# PCB-BI8-2x8.net
KiCad netlist of a schematic drawn in EAGLE
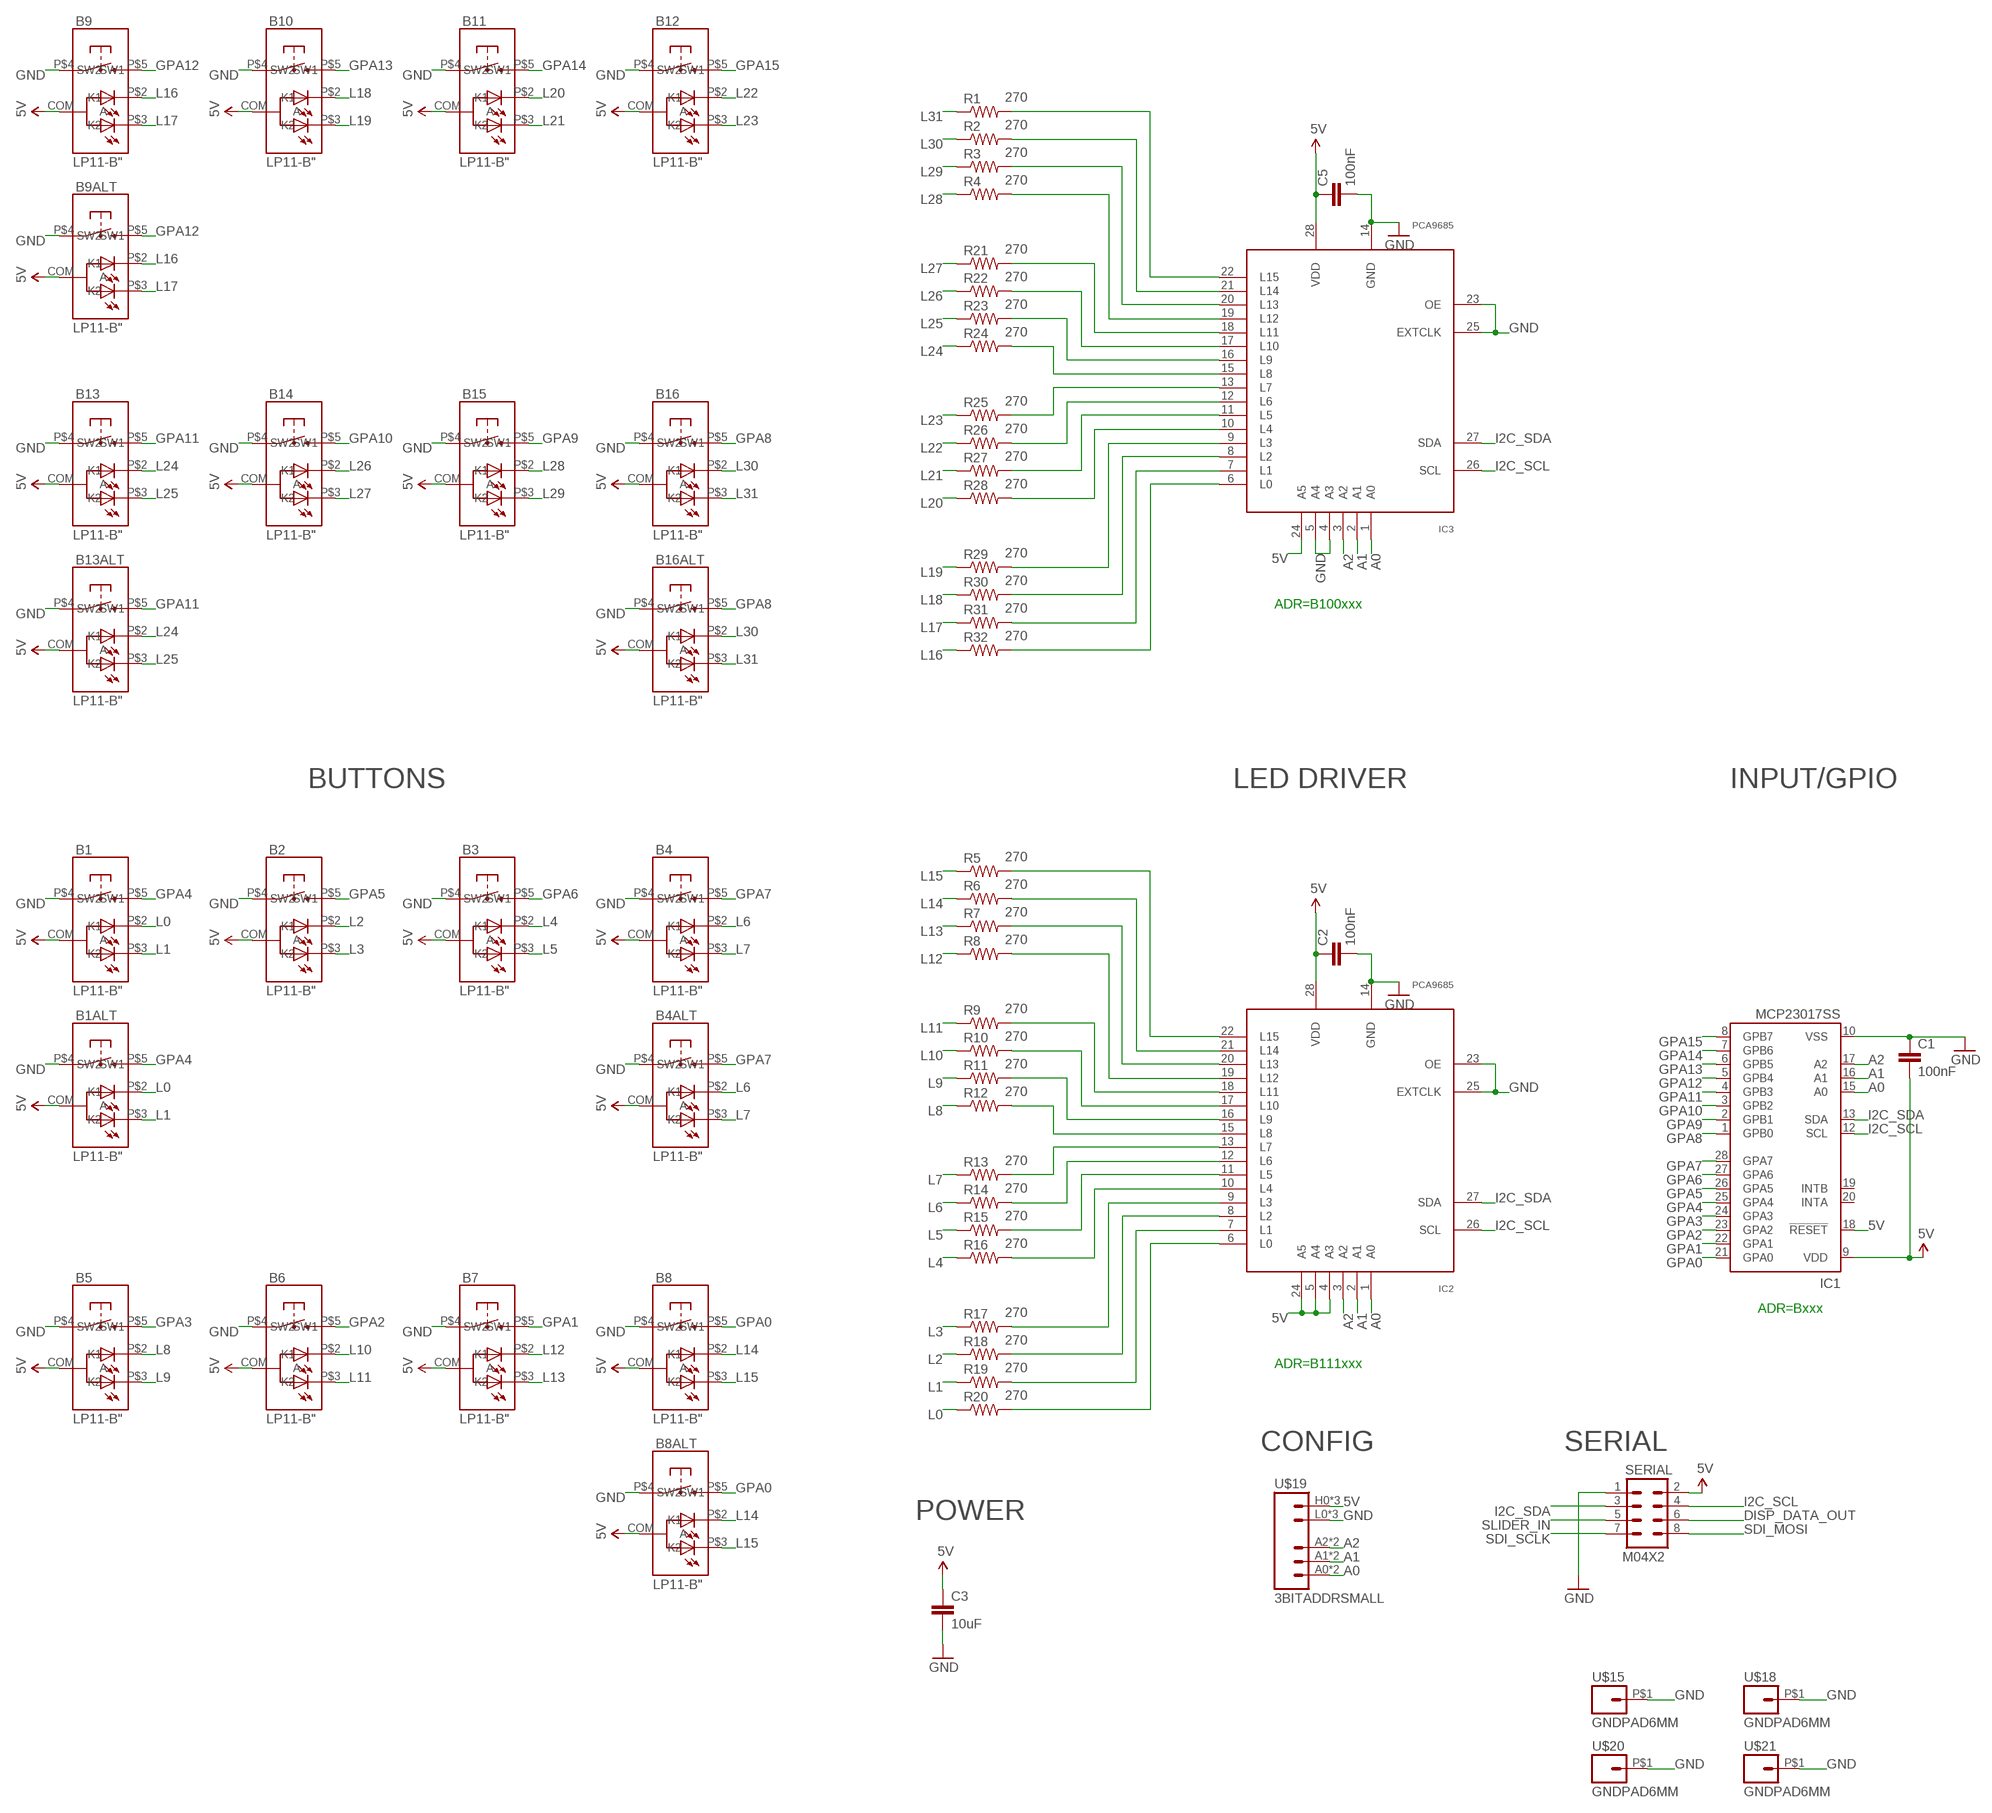
[diagram p0: schematic, sheet 1]

(export (version "E")
  (design (tool "Eeschema 10.0.6"))
  (components
    (comp (ref "B1")
      (value "LP11-B\"")
      (footprint "eagle-import:LP11")
      (libsource (lib "eagle-import") (part "LP11-B{dblquote}"))
    )
    (comp (ref "B1ALT")
      (value "LP11-B\"")
      (footprint "eagle-import:LP11")
      (libsource (lib "eagle-import") (part "LP11-B{dblquote}"))
    )
    (comp (ref "B2")
      (value "LP11-B\"")
      (footprint "eagle-import:LP11")
      (libsource (lib "eagle-import") (part "LP11-B{dblquote}"))
    )
    (comp (ref "B3")
      (value "LP11-B\"")
      (footprint "eagle-import:LP11")
      (libsource (lib "eagle-import") (part "LP11-B{dblquote}"))
    )
    (comp (ref "B4")
      (value "LP11-B\"")
      (footprint "eagle-import:LP11")
      (libsource (lib "eagle-import") (part "LP11-B{dblquote}"))
    )
    (comp (ref "B4ALT")
      (value "LP11-B\"")
      (footprint "eagle-import:LP11")
      (libsource (lib "eagle-import") (part "LP11-B{dblquote}"))
    )
    (comp (ref "B5")
      (value "LP11-B\"")
      (footprint "eagle-import:LP11")
      (libsource (lib "eagle-import") (part "LP11-B{dblquote}"))
    )
    (comp (ref "B6")
      (value "LP11-B\"")
      (footprint "eagle-import:LP11")
      (libsource (lib "eagle-import") (part "LP11-B{dblquote}"))
    )
    (comp (ref "B7")
      (value "LP11-B\"")
      (footprint "eagle-import:LP11")
      (libsource (lib "eagle-import") (part "LP11-B{dblquote}"))
    )
    (comp (ref "B8")
      (value "LP11-B\"")
      (footprint "eagle-import:LP11")
      (libsource (lib "eagle-import") (part "LP11-B{dblquote}"))
    )
    (comp (ref "B8ALT")
      (value "LP11-B\"")
      (footprint "eagle-import:LP11")
      (libsource (lib "eagle-import") (part "LP11-B{dblquote}"))
    )
    (comp (ref "B9")
      (value "LP11-B\"")
      (footprint "eagle-import:LP11")
      (libsource (lib "eagle-import") (part "LP11-B{dblquote}"))
    )
    (comp (ref "B9ALT")
      (value "LP11-B\"")
      (footprint "eagle-import:LP11")
      (libsource (lib "eagle-import") (part "LP11-B{dblquote}"))
    )
    (comp (ref "B10")
      (value "LP11-B\"")
      (footprint "eagle-import:LP11")
      (libsource (lib "eagle-import") (part "LP11-B{dblquote}"))
    )
    (comp (ref "B11")
      (value "LP11-B\"")
      (footprint "eagle-import:LP11")
      (libsource (lib "eagle-import") (part "LP11-B{dblquote}"))
    )
    (comp (ref "B12")
      (value "LP11-B\"")
      (footprint "eagle-import:LP11")
      (libsource (lib "eagle-import") (part "LP11-B{dblquote}"))
    )
    (comp (ref "B13")
      (value "LP11-B\"")
      (footprint "eagle-import:LP11")
      (libsource (lib "eagle-import") (part "LP11-B{dblquote}"))
    )
    (comp (ref "B13ALT")
      (value "LP11-B\"")
      (footprint "eagle-import:LP11")
      (libsource (lib "eagle-import") (part "LP11-B{dblquote}"))
    )
    (comp (ref "B14")
      (value "LP11-B\"")
      (footprint "eagle-import:LP11")
      (libsource (lib "eagle-import") (part "LP11-B{dblquote}"))
    )
    (comp (ref "B15")
      (value "LP11-B\"")
      (footprint "eagle-import:LP11")
      (libsource (lib "eagle-import") (part "LP11-B{dblquote}"))
    )
    (comp (ref "B16")
      (value "LP11-B\"")
      (footprint "eagle-import:LP11")
      (libsource (lib "eagle-import") (part "LP11-B{dblquote}"))
    )
    (comp (ref "B16ALT")
      (value "LP11-B\"")
      (footprint "eagle-import:LP11")
      (libsource (lib "eagle-import") (part "LP11-B{dblquote}"))
    )
    (comp (ref "C1")
      (value "100nF")
      (footprint "eagle-import:0603-CAP")
      (libsource (lib "eagle-import") (part "CAP0603-CAP"))
    )
    (comp (ref "C2")
      (value "100nF")
      (footprint "eagle-import:0603-CAP")
      (libsource (lib "eagle-import") (part "CAP0603-CAP"))
    )
    (comp (ref "C3")
      (value "10uF")
      (footprint "eagle-import:0805")
      (libsource (lib "eagle-import") (part "CAP0805"))
    )
    (comp (ref "C5")
      (value "100nF")
      (footprint "eagle-import:0603-CAP")
      (libsource (lib "eagle-import") (part "CAP0603-CAP"))
    )
    (comp (ref "IC1")
      (value "MCP23017SS")
      (footprint "eagle-import:SSOP28")
      (fields
        (field (name "MF") "MICROCHIP")
        (field (name "MPN") "MCP23017-E/SS")
        (field (name "MPN_1") "MCP23017-E/SS")
        (field (name "OC_FARNELL") "1467674")
        (field (name "OC_NEWARK") "31K2960")
      )
      (libsource (lib "eagle-import") (part "MCP23017SS"))
    )
    (comp (ref "IC2")
      (value "PCA9685")
      (footprint "eagle-import:TSSOP28")
      (libsource (lib "eagle-import") (part "PCA9685"))
    )
    (comp (ref "IC3")
      (value "PCA9685")
      (footprint "eagle-import:TSSOP28")
      (libsource (lib "eagle-import") (part "PCA9685"))
    )
    (comp (ref "R1")
      (value "270")
      (footprint "eagle-import:0603-RES")
      (libsource (lib "eagle-import") (part "RESISTOR0603-RES"))
    )
    (comp (ref "R2")
      (value "270")
      (footprint "eagle-import:0603-RES")
      (libsource (lib "eagle-import") (part "RESISTOR0603-RES"))
    )
    (comp (ref "R3")
      (value "270")
      (footprint "eagle-import:0603-RES")
      (libsource (lib "eagle-import") (part "RESISTOR0603-RES"))
    )
    (comp (ref "R4")
      (value "270")
      (footprint "eagle-import:0603-RES")
      (libsource (lib "eagle-import") (part "RESISTOR0603-RES"))
    )
    (comp (ref "R5")
      (value "270")
      (footprint "eagle-import:0603-RES")
      (libsource (lib "eagle-import") (part "RESISTOR0603-RES"))
    )
    (comp (ref "R6")
      (value "270")
      (footprint "eagle-import:0603-RES")
      (libsource (lib "eagle-import") (part "RESISTOR0603-RES"))
    )
    (comp (ref "R7")
      (value "270")
      (footprint "eagle-import:0603-RES")
      (libsource (lib "eagle-import") (part "RESISTOR0603-RES"))
    )
    (comp (ref "R8")
      (value "270")
      (footprint "eagle-import:0603-RES")
      (libsource (lib "eagle-import") (part "RESISTOR0603-RES"))
    )
    (comp (ref "R9")
      (value "270")
      (footprint "eagle-import:0603-RES")
      (libsource (lib "eagle-import") (part "RESISTOR0603-RES"))
    )
    (comp (ref "R10")
      (value "270")
      (footprint "eagle-import:0603-RES")
      (libsource (lib "eagle-import") (part "RESISTOR0603-RES"))
    )
    (comp (ref "R11")
      (value "270")
      (footprint "eagle-import:0603-RES")
      (libsource (lib "eagle-import") (part "RESISTOR0603-RES"))
    )
    (comp (ref "R12")
      (value "270")
      (footprint "eagle-import:0603-RES")
      (libsource (lib "eagle-import") (part "RESISTOR0603-RES"))
    )
    (comp (ref "R13")
      (value "270")
      (footprint "eagle-import:0603-RES")
      (libsource (lib "eagle-import") (part "RESISTOR0603-RES"))
    )
    (comp (ref "R14")
      (value "270")
      (footprint "eagle-import:0603-RES")
      (libsource (lib "eagle-import") (part "RESISTOR0603-RES"))
    )
    (comp (ref "R15")
      (value "270")
      (footprint "eagle-import:0603-RES")
      (libsource (lib "eagle-import") (part "RESISTOR0603-RES"))
    )
    (comp (ref "R16")
      (value "270")
      (footprint "eagle-import:0603-RES")
      (libsource (lib "eagle-import") (part "RESISTOR0603-RES"))
    )
    (comp (ref "R17")
      (value "270")
      (footprint "eagle-import:0603-RES")
      (libsource (lib "eagle-import") (part "RESISTOR0603-RES"))
    )
    (comp (ref "R18")
      (value "270")
      (footprint "eagle-import:0603-RES")
      (libsource (lib "eagle-import") (part "RESISTOR0603-RES"))
    )
    (comp (ref "R19")
      (value "270")
      (footprint "eagle-import:0603-RES")
      (libsource (lib "eagle-import") (part "RESISTOR0603-RES"))
    )
    (comp (ref "R20")
      (value "270")
      (footprint "eagle-import:0603-RES")
      (libsource (lib "eagle-import") (part "RESISTOR0603-RES"))
    )
    (comp (ref "R21")
      (value "270")
      (footprint "eagle-import:0603-RES")
      (libsource (lib "eagle-import") (part "RESISTOR0603-RES"))
    )
    (comp (ref "R22")
      (value "270")
      (footprint "eagle-import:0603-RES")
      (libsource (lib "eagle-import") (part "RESISTOR0603-RES"))
    )
    (comp (ref "R23")
      (value "270")
      (footprint "eagle-import:0603-RES")
      (libsource (lib "eagle-import") (part "RESISTOR0603-RES"))
    )
    (comp (ref "R24")
      (value "270")
      (footprint "eagle-import:0603-RES")
      (libsource (lib "eagle-import") (part "RESISTOR0603-RES"))
    )
    (comp (ref "R25")
      (value "270")
      (footprint "eagle-import:0603-RES")
      (libsource (lib "eagle-import") (part "RESISTOR0603-RES"))
    )
    (comp (ref "R26")
      (value "270")
      (footprint "eagle-import:0603-RES")
      (libsource (lib "eagle-import") (part "RESISTOR0603-RES"))
    )
    (comp (ref "R27")
      (value "270")
      (footprint "eagle-import:0603-RES")
      (libsource (lib "eagle-import") (part "RESISTOR0603-RES"))
    )
    (comp (ref "R28")
      (value "270")
      (footprint "eagle-import:0603-RES")
      (libsource (lib "eagle-import") (part "RESISTOR0603-RES"))
    )
    (comp (ref "R29")
      (value "270")
      (footprint "eagle-import:0603-RES")
      (libsource (lib "eagle-import") (part "RESISTOR0603-RES"))
    )
    (comp (ref "R30")
      (value "270")
      (footprint "eagle-import:0603-RES")
      (libsource (lib "eagle-import") (part "RESISTOR0603-RES"))
    )
    (comp (ref "R31")
      (value "270")
      (footprint "eagle-import:0603-RES")
      (libsource (lib "eagle-import") (part "RESISTOR0603-RES"))
    )
    (comp (ref "R32")
      (value "270")
      (footprint "eagle-import:0603-RES")
      (libsource (lib "eagle-import") (part "RESISTOR0603-RES"))
    )
    (comp (ref "SERIAL")
      (value "M04X2")
      (footprint "eagle-import:2X4")
      (libsource (lib "eagle-import") (part "M04X2"))
    )
    (comp (ref "U$15")
      (value "GNDPAD6MM")
      (footprint "eagle-import:3.2MMPAD6MM")
      (libsource (lib "eagle-import") (part "GNDPAD6MM"))
    )
    (comp (ref "U$18")
      (value "GNDPAD6MM")
      (footprint "eagle-import:3.2MMPAD6MM")
      (libsource (lib "eagle-import") (part "GNDPAD6MM"))
    )
    (comp (ref "U$19")
      (value "3BITADDRSMALL")
      (footprint "eagle-import:3BITADDR_SMALL")
      (libsource (lib "eagle-import") (part "3BITADDRSMALL"))
    )
    (comp (ref "U$20")
      (value "GNDPAD6MM")
      (footprint "eagle-import:3.2MMPAD6MM")
      (libsource (lib "eagle-import") (part "GNDPAD6MM"))
    )
    (comp (ref "U$21")
      (value "GNDPAD6MM")
      (footprint "eagle-import:3.2MMPAD6MM")
      (libsource (lib "eagle-import") (part "GNDPAD6MM"))
    )
  )
  (nets
    (net (code "1") (name "5V") (class "Default")
      (node (ref "B1") (pin "COM") (pinfunction "A_COM") (pintype "bidirectional"))
      (node (ref "B10") (pin "COM") (pinfunction "A_COM") (pintype "bidirectional"))
      (node (ref "B11") (pin "COM") (pinfunction "A_COM") (pintype "bidirectional"))
      (node (ref "B12") (pin "COM") (pinfunction "A_COM") (pintype "bidirectional"))
      (node (ref "B13") (pin "COM") (pinfunction "A_COM") (pintype "bidirectional"))
      (node (ref "B13ALT") (pin "COM") (pinfunction "A_COM") (pintype "bidirectional"))
      (node (ref "B14") (pin "COM") (pinfunction "A_COM") (pintype "bidirectional"))
      (node (ref "B15") (pin "COM") (pinfunction "A_COM") (pintype "bidirectional"))
      (node (ref "B16") (pin "COM") (pinfunction "A_COM") (pintype "bidirectional"))
      (node (ref "B16ALT") (pin "COM") (pinfunction "A_COM") (pintype "bidirectional"))
      (node (ref "B1ALT") (pin "COM") (pinfunction "A_COM") (pintype "bidirectional"))
      (node (ref "B2") (pin "COM") (pinfunction "A_COM") (pintype "bidirectional"))
      (node (ref "B3") (pin "COM") (pinfunction "A_COM") (pintype "bidirectional"))
      (node (ref "B4") (pin "COM") (pinfunction "A_COM") (pintype "bidirectional"))
      (node (ref "B4ALT") (pin "COM") (pinfunction "A_COM") (pintype "bidirectional"))
      (node (ref "B5") (pin "COM") (pinfunction "A_COM") (pintype "bidirectional"))
      (node (ref "B6") (pin "COM") (pinfunction "A_COM") (pintype "bidirectional"))
      (node (ref "B7") (pin "COM") (pinfunction "A_COM") (pintype "bidirectional"))
      (node (ref "B8") (pin "COM") (pinfunction "A_COM") (pintype "bidirectional"))
      (node (ref "B8ALT") (pin "COM") (pinfunction "A_COM") (pintype "bidirectional"))
      (node (ref "B9") (pin "COM") (pinfunction "A_COM") (pintype "bidirectional"))
      (node (ref "B9ALT") (pin "COM") (pinfunction "A_COM") (pintype "bidirectional"))
      (node (ref "C1") (pin "2") (pinfunction "2_2") (pintype "passive"))
      (node (ref "C2") (pin "1") (pinfunction "1_1") (pintype "passive"))
      (node (ref "C3") (pin "1") (pinfunction "1_1") (pintype "passive"))
      (node (ref "C5") (pin "1") (pinfunction "1_1") (pintype "passive"))
      (node (ref "IC1") (pin "18") (pinfunction "~{RESET}_18") (pintype "input"))
      (node (ref "IC1") (pin "9") (pinfunction "VDD_9") (pintype "power_in"))
      (node (ref "IC2") (pin "24") (pinfunction "A5_24") (pintype "input"))
      (node (ref "IC2") (pin "28") (pinfunction "VDD_28") (pintype "power_in"))
      (node (ref "IC2") (pin "4") (pinfunction "A3_4") (pintype "input"))
      (node (ref "IC2") (pin "5") (pinfunction "A4_5") (pintype "input"))
      (node (ref "IC3") (pin "24") (pinfunction "A5_24") (pintype "input"))
      (node (ref "IC3") (pin "28") (pinfunction "VDD_28") (pintype "power_in"))
      (node (ref "SERIAL") (pin "2") (pinfunction "2_2") (pintype "passive"))
      (node (ref "U$19") (pin "H0") (pinfunction "VCC_H0") (pintype "passive"))
      (node (ref "U$19") (pin "H1") (pinfunction "VCC_H1") (pintype "passive"))
      (node (ref "U$19") (pin "H2") (pinfunction "VCC_H2") (pintype "passive"))
    )
    (net (code "2") (name "A0") (class "Default")
      (node (ref "IC1") (pin "15") (pinfunction "A0_15") (pintype "input"))
      (node (ref "IC2") (pin "1") (pinfunction "A0_1") (pintype "input"))
      (node (ref "IC3") (pin "1") (pinfunction "A0_1") (pintype "input"))
      (node (ref "U$19") (pin "A0") (pinfunction "A0_A0") (pintype "passive"))
      (node (ref "U$19") (pin "AS0") (pinfunction "A0_AS0") (pintype "passive"))
    )
    (net (code "3") (name "A1") (class "Default")
      (node (ref "IC1") (pin "16") (pinfunction "A1_16") (pintype "input"))
      (node (ref "IC2") (pin "2") (pinfunction "A1_2") (pintype "input"))
      (node (ref "IC3") (pin "2") (pinfunction "A1_2") (pintype "input"))
      (node (ref "U$19") (pin "A1") (pinfunction "A1_A1") (pintype "passive"))
      (node (ref "U$19") (pin "AS1") (pinfunction "A1_AS1") (pintype "passive"))
    )
    (net (code "4") (name "A2") (class "Default")
      (node (ref "IC1") (pin "17") (pinfunction "A2_17") (pintype "input"))
      (node (ref "IC2") (pin "3") (pinfunction "A2_3") (pintype "input"))
      (node (ref "IC3") (pin "3") (pinfunction "A2_3") (pintype "input"))
      (node (ref "U$19") (pin "A2") (pinfunction "A2_A2") (pintype "passive"))
      (node (ref "U$19") (pin "AS2") (pinfunction "A2_AS2") (pintype "passive"))
    )
    (net (code "5") (name "DISP_DATA_OUT") (class "Default")
      (node (ref "SERIAL") (pin "6") (pinfunction "6_6") (pintype "passive"))
    )
    (net (code "6") (name "GND") (class "Default")
      (node (ref "B1") (pin "P$4") (pinfunction "SW1_P$4") (pintype "bidirectional"))
      (node (ref "B10") (pin "P$4") (pinfunction "SW1_P$4") (pintype "bidirectional"))
      (node (ref "B11") (pin "P$4") (pinfunction "SW1_P$4") (pintype "bidirectional"))
      (node (ref "B12") (pin "P$4") (pinfunction "SW1_P$4") (pintype "bidirectional"))
      (node (ref "B13") (pin "P$4") (pinfunction "SW1_P$4") (pintype "bidirectional"))
      (node (ref "B13ALT") (pin "P$4") (pinfunction "SW1_P$4") (pintype "bidirectional"))
      (node (ref "B14") (pin "P$4") (pinfunction "SW1_P$4") (pintype "bidirectional"))
      (node (ref "B15") (pin "P$4") (pinfunction "SW1_P$4") (pintype "bidirectional"))
      (node (ref "B16") (pin "P$4") (pinfunction "SW1_P$4") (pintype "bidirectional"))
      (node (ref "B16ALT") (pin "P$4") (pinfunction "SW1_P$4") (pintype "bidirectional"))
      (node (ref "B1ALT") (pin "P$4") (pinfunction "SW1_P$4") (pintype "bidirectional"))
      (node (ref "B2") (pin "P$4") (pinfunction "SW1_P$4") (pintype "bidirectional"))
      (node (ref "B3") (pin "P$4") (pinfunction "SW1_P$4") (pintype "bidirectional"))
      (node (ref "B4") (pin "P$4") (pinfunction "SW1_P$4") (pintype "bidirectional"))
      (node (ref "B4ALT") (pin "P$4") (pinfunction "SW1_P$4") (pintype "bidirectional"))
      (node (ref "B5") (pin "P$4") (pinfunction "SW1_P$4") (pintype "bidirectional"))
      (node (ref "B6") (pin "P$4") (pinfunction "SW1_P$4") (pintype "bidirectional"))
      (node (ref "B7") (pin "P$4") (pinfunction "SW1_P$4") (pintype "bidirectional"))
      (node (ref "B8") (pin "P$4") (pinfunction "SW1_P$4") (pintype "bidirectional"))
      (node (ref "B8ALT") (pin "P$4") (pinfunction "SW1_P$4") (pintype "bidirectional"))
      (node (ref "B9") (pin "P$4") (pinfunction "SW1_P$4") (pintype "bidirectional"))
      (node (ref "B9ALT") (pin "P$4") (pinfunction "SW1_P$4") (pintype "bidirectional"))
      (node (ref "C1") (pin "1") (pinfunction "1_1") (pintype "passive"))
      (node (ref "C2") (pin "2") (pinfunction "2_2") (pintype "passive"))
      (node (ref "C3") (pin "2") (pinfunction "2_2") (pintype "passive"))
      (node (ref "C5") (pin "2") (pinfunction "2_2") (pintype "passive"))
      (node (ref "IC1") (pin "10") (pinfunction "VSS_10") (pintype "power_in"))
      (node (ref "IC2") (pin "14") (pinfunction "GND_14") (pintype "power_in"))
      (node (ref "IC2") (pin "23") (pinfunction "OE_23") (pintype "input"))
      (node (ref "IC2") (pin "25") (pinfunction "EXTCLK_25") (pintype "input"))
      (node (ref "IC3") (pin "14") (pinfunction "GND_14") (pintype "power_in"))
      (node (ref "IC3") (pin "23") (pinfunction "OE_23") (pintype "input"))
      (node (ref "IC3") (pin "25") (pinfunction "EXTCLK_25") (pintype "input"))
      (node (ref "IC3") (pin "4") (pinfunction "A3_4") (pintype "input"))
      (node (ref "IC3") (pin "5") (pinfunction "A4_5") (pintype "input"))
      (node (ref "SERIAL") (pin "1") (pinfunction "1_1") (pintype "passive"))
      (node (ref "U$15") (pin "P$1") (pinfunction "1_P$1") (pintype "passive"))
      (node (ref "U$18") (pin "P$1") (pinfunction "1_P$1") (pintype "passive"))
      (node (ref "U$19") (pin "L0") (pinfunction "GND_L0") (pintype "passive"))
      (node (ref "U$19") (pin "L1") (pinfunction "GND_L1") (pintype "passive"))
      (node (ref "U$19") (pin "L2") (pinfunction "GND_L2") (pintype "passive"))
      (node (ref "U$20") (pin "P$1") (pinfunction "1_P$1") (pintype "passive"))
      (node (ref "U$21") (pin "P$1") (pinfunction "1_P$1") (pintype "passive"))
    )
    (net (code "7") (name "GPA0") (class "Default")
      (node (ref "B8") (pin "P$5") (pinfunction "SW2_P$5") (pintype "bidirectional"))
      (node (ref "B8ALT") (pin "P$5") (pinfunction "SW2_P$5") (pintype "bidirectional"))
      (node (ref "IC1") (pin "21") (pinfunction "GPA0_21") (pintype "bidirectional"))
    )
    (net (code "8") (name "GPA1") (class "Default")
      (node (ref "B7") (pin "P$5") (pinfunction "SW2_P$5") (pintype "bidirectional"))
      (node (ref "IC1") (pin "22") (pinfunction "GPA1_22") (pintype "bidirectional"))
    )
    (net (code "9") (name "GPA2") (class "Default")
      (node (ref "B6") (pin "P$5") (pinfunction "SW2_P$5") (pintype "bidirectional"))
      (node (ref "IC1") (pin "23") (pinfunction "GPA2_23") (pintype "bidirectional"))
    )
    (net (code "10") (name "GPA3") (class "Default")
      (node (ref "B5") (pin "P$5") (pinfunction "SW2_P$5") (pintype "bidirectional"))
      (node (ref "IC1") (pin "24") (pinfunction "GPA3_24") (pintype "bidirectional"))
    )
    (net (code "11") (name "GPA4") (class "Default")
      (node (ref "B1") (pin "P$5") (pinfunction "SW2_P$5") (pintype "bidirectional"))
      (node (ref "B1ALT") (pin "P$5") (pinfunction "SW2_P$5") (pintype "bidirectional"))
      (node (ref "IC1") (pin "25") (pinfunction "GPA4_25") (pintype "bidirectional"))
    )
    (net (code "12") (name "GPA5") (class "Default")
      (node (ref "B2") (pin "P$5") (pinfunction "SW2_P$5") (pintype "bidirectional"))
      (node (ref "IC1") (pin "26") (pinfunction "GPA5_26") (pintype "bidirectional"))
    )
    (net (code "13") (name "GPA6") (class "Default")
      (node (ref "B3") (pin "P$5") (pinfunction "SW2_P$5") (pintype "bidirectional"))
      (node (ref "IC1") (pin "27") (pinfunction "GPA6_27") (pintype "bidirectional"))
    )
    (net (code "14") (name "GPA7") (class "Default")
      (node (ref "B4") (pin "P$5") (pinfunction "SW2_P$5") (pintype "bidirectional"))
      (node (ref "B4ALT") (pin "P$5") (pinfunction "SW2_P$5") (pintype "bidirectional"))
      (node (ref "IC1") (pin "28") (pinfunction "GPA7_28") (pintype "bidirectional"))
    )
    (net (code "15") (name "GPA8") (class "Default")
      (node (ref "B16") (pin "P$5") (pinfunction "SW2_P$5") (pintype "bidirectional"))
      (node (ref "B16ALT") (pin "P$5") (pinfunction "SW2_P$5") (pintype "bidirectional"))
      (node (ref "IC1") (pin "1") (pinfunction "GPB0_1") (pintype "bidirectional"))
    )
    (net (code "16") (name "GPA9") (class "Default")
      (node (ref "B15") (pin "P$5") (pinfunction "SW2_P$5") (pintype "bidirectional"))
      (node (ref "IC1") (pin "2") (pinfunction "GPB1_2") (pintype "bidirectional"))
    )
    (net (code "17") (name "GPA10") (class "Default")
      (node (ref "B14") (pin "P$5") (pinfunction "SW2_P$5") (pintype "bidirectional"))
      (node (ref "IC1") (pin "3") (pinfunction "GPB2_3") (pintype "bidirectional"))
    )
    (net (code "18") (name "GPA11") (class "Default")
      (node (ref "B13") (pin "P$5") (pinfunction "SW2_P$5") (pintype "bidirectional"))
      (node (ref "B13ALT") (pin "P$5") (pinfunction "SW2_P$5") (pintype "bidirectional"))
      (node (ref "IC1") (pin "4") (pinfunction "GPB3_4") (pintype "bidirectional"))
    )
    (net (code "19") (name "GPA12") (class "Default")
      (node (ref "B9") (pin "P$5") (pinfunction "SW2_P$5") (pintype "bidirectional"))
      (node (ref "B9ALT") (pin "P$5") (pinfunction "SW2_P$5") (pintype "bidirectional"))
      (node (ref "IC1") (pin "5") (pinfunction "GPB4_5") (pintype "bidirectional"))
    )
    (net (code "20") (name "GPA13") (class "Default")
      (node (ref "B10") (pin "P$5") (pinfunction "SW2_P$5") (pintype "bidirectional"))
      (node (ref "IC1") (pin "6") (pinfunction "GPB5_6") (pintype "bidirectional"))
    )
    (net (code "21") (name "GPA14") (class "Default")
      (node (ref "B11") (pin "P$5") (pinfunction "SW2_P$5") (pintype "bidirectional"))
      (node (ref "IC1") (pin "7") (pinfunction "GPB6_7") (pintype "bidirectional"))
    )
    (net (code "22") (name "GPA15") (class "Default")
      (node (ref "B12") (pin "P$5") (pinfunction "SW2_P$5") (pintype "bidirectional"))
      (node (ref "IC1") (pin "8") (pinfunction "GPB7_8") (pintype "bidirectional"))
    )
    (net (code "23") (name "I2C_SCL") (class "Default")
      (node (ref "IC1") (pin "12") (pinfunction "SCL_12") (pintype "input"))
      (node (ref "IC2") (pin "26") (pinfunction "SCL_26") (pintype "input"))
      (node (ref "IC3") (pin "26") (pinfunction "SCL_26") (pintype "input"))
      (node (ref "SERIAL") (pin "4") (pinfunction "4_4") (pintype "passive"))
    )
    (net (code "24") (name "I2C_SDA") (class "Default")
      (node (ref "IC1") (pin "13") (pinfunction "SDA_13") (pintype "bidirectional"))
      (node (ref "IC2") (pin "27") (pinfunction "SDA_27") (pintype "input"))
      (node (ref "IC3") (pin "27") (pinfunction "SDA_27") (pintype "input"))
      (node (ref "SERIAL") (pin "3") (pinfunction "3_3") (pintype "passive"))
    )
    (net (code "25") (name "L0") (class "Default")
      (node (ref "B1") (pin "P$2") (pinfunction "K1_P$2") (pintype "bidirectional"))
      (node (ref "B1ALT") (pin "P$2") (pinfunction "K1_P$2") (pintype "bidirectional"))
      (node (ref "R20") (pin "1") (pinfunction "1_1") (pintype "passive"))
    )
    (net (code "26") (name "L1") (class "Default")
      (node (ref "B1") (pin "P$3") (pinfunction "K2_P$3") (pintype "bidirectional"))
      (node (ref "B1ALT") (pin "P$3") (pinfunction "K2_P$3") (pintype "bidirectional"))
      (node (ref "R19") (pin "1") (pinfunction "1_1") (pintype "passive"))
    )
    (net (code "27") (name "L2") (class "Default")
      (node (ref "B2") (pin "P$2") (pinfunction "K1_P$2") (pintype "bidirectional"))
      (node (ref "R18") (pin "1") (pinfunction "1_1") (pintype "passive"))
    )
    (net (code "28") (name "L3") (class "Default")
      (node (ref "B2") (pin "P$3") (pinfunction "K2_P$3") (pintype "bidirectional"))
      (node (ref "R17") (pin "1") (pinfunction "1_1") (pintype "passive"))
    )
    (net (code "29") (name "L4") (class "Default")
      (node (ref "B3") (pin "P$2") (pinfunction "K1_P$2") (pintype "bidirectional"))
      (node (ref "R16") (pin "1") (pinfunction "1_1") (pintype "passive"))
    )
    (net (code "30") (name "L5") (class "Default")
      (node (ref "B3") (pin "P$3") (pinfunction "K2_P$3") (pintype "bidirectional"))
      (node (ref "R15") (pin "1") (pinfunction "1_1") (pintype "passive"))
    )
    (net (code "31") (name "L6") (class "Default")
      (node (ref "B4") (pin "P$2") (pinfunction "K1_P$2") (pintype "bidirectional"))
      (node (ref "B4ALT") (pin "P$2") (pinfunction "K1_P$2") (pintype "bidirectional"))
      (node (ref "R14") (pin "1") (pinfunction "1_1") (pintype "passive"))
    )
    (net (code "32") (name "L7") (class "Default")
      (node (ref "B4") (pin "P$3") (pinfunction "K2_P$3") (pintype "bidirectional"))
      (node (ref "B4ALT") (pin "P$3") (pinfunction "K2_P$3") (pintype "bidirectional"))
      (node (ref "R13") (pin "1") (pinfunction "1_1") (pintype "passive"))
    )
    (net (code "33") (name "L8") (class "Default")
      (node (ref "B5") (pin "P$2") (pinfunction "K1_P$2") (pintype "bidirectional"))
      (node (ref "R12") (pin "1") (pinfunction "1_1") (pintype "passive"))
    )
    (net (code "34") (name "L9") (class "Default")
      (node (ref "B5") (pin "P$3") (pinfunction "K2_P$3") (pintype "bidirectional"))
      (node (ref "R11") (pin "1") (pinfunction "1_1") (pintype "passive"))
    )
    (net (code "35") (name "L10") (class "Default")
      (node (ref "B6") (pin "P$2") (pinfunction "K1_P$2") (pintype "bidirectional"))
      (node (ref "R10") (pin "1") (pinfunction "1_1") (pintype "passive"))
    )
    (net (code "36") (name "L11") (class "Default")
      (node (ref "B6") (pin "P$3") (pinfunction "K2_P$3") (pintype "bidirectional"))
      (node (ref "R9") (pin "1") (pinfunction "1_1") (pintype "passive"))
    )
    (net (code "37") (name "L12") (class "Default")
      (node (ref "B7") (pin "P$2") (pinfunction "K1_P$2") (pintype "bidirectional"))
      (node (ref "R8") (pin "1") (pinfunction "1_1") (pintype "passive"))
    )
    (net (code "38") (name "L13") (class "Default")
      (node (ref "B7") (pin "P$3") (pinfunction "K2_P$3") (pintype "bidirectional"))
      (node (ref "R7") (pin "1") (pinfunction "1_1") (pintype "passive"))
    )
    (net (code "39") (name "L14") (class "Default")
      (node (ref "B8") (pin "P$2") (pinfunction "K1_P$2") (pintype "bidirectional"))
      (node (ref "B8ALT") (pin "P$2") (pinfunction "K1_P$2") (pintype "bidirectional"))
      (node (ref "R6") (pin "1") (pinfunction "1_1") (pintype "passive"))
    )
    (net (code "40") (name "L15") (class "Default")
      (node (ref "B8") (pin "P$3") (pinfunction "K2_P$3") (pintype "bidirectional"))
      (node (ref "B8ALT") (pin "P$3") (pinfunction "K2_P$3") (pintype "bidirectional"))
      (node (ref "R5") (pin "1") (pinfunction "1_1") (pintype "passive"))
    )
    (net (code "41") (name "L16") (class "Default")
      (node (ref "B9") (pin "P$2") (pinfunction "K1_P$2") (pintype "bidirectional"))
      (node (ref "B9ALT") (pin "P$2") (pinfunction "K1_P$2") (pintype "bidirectional"))
      (node (ref "R32") (pin "1") (pinfunction "1_1") (pintype "passive"))
    )
    (net (code "42") (name "L17") (class "Default")
      (node (ref "B9") (pin "P$3") (pinfunction "K2_P$3") (pintype "bidirectional"))
      (node (ref "B9ALT") (pin "P$3") (pinfunction "K2_P$3") (pintype "bidirectional"))
      (node (ref "R31") (pin "1") (pinfunction "1_1") (pintype "passive"))
    )
    (net (code "43") (name "L18") (class "Default")
      (node (ref "B10") (pin "P$2") (pinfunction "K1_P$2") (pintype "bidirectional"))
      (node (ref "R30") (pin "1") (pinfunction "1_1") (pintype "passive"))
    )
    (net (code "44") (name "L19") (class "Default")
      (node (ref "B10") (pin "P$3") (pinfunction "K2_P$3") (pintype "bidirectional"))
      (node (ref "R29") (pin "1") (pinfunction "1_1") (pintype "passive"))
    )
    (net (code "45") (name "L20") (class "Default")
      (node (ref "B11") (pin "P$2") (pinfunction "K1_P$2") (pintype "bidirectional"))
      (node (ref "R28") (pin "1") (pinfunction "1_1") (pintype "passive"))
    )
    (net (code "46") (name "L21") (class "Default")
      (node (ref "B11") (pin "P$3") (pinfunction "K2_P$3") (pintype "bidirectional"))
      (node (ref "R27") (pin "1") (pinfunction "1_1") (pintype "passive"))
    )
    (net (code "47") (name "L22") (class "Default")
      (node (ref "B12") (pin "P$2") (pinfunction "K1_P$2") (pintype "bidirectional"))
      (node (ref "R26") (pin "1") (pinfunction "1_1") (pintype "passive"))
    )
    (net (code "48") (name "L23") (class "Default")
      (node (ref "B12") (pin "P$3") (pinfunction "K2_P$3") (pintype "bidirectional"))
      (node (ref "R25") (pin "1") (pinfunction "1_1") (pintype "passive"))
    )
    (net (code "49") (name "L24") (class "Default")
      (node (ref "B13") (pin "P$2") (pinfunction "K1_P$2") (pintype "bidirectional"))
      (node (ref "B13ALT") (pin "P$2") (pinfunction "K1_P$2") (pintype "bidirectional"))
      (node (ref "R24") (pin "1") (pinfunction "1_1") (pintype "passive"))
    )
    (net (code "50") (name "L25") (class "Default")
      (node (ref "B13") (pin "P$3") (pinfunction "K2_P$3") (pintype "bidirectional"))
      (node (ref "B13ALT") (pin "P$3") (pinfunction "K2_P$3") (pintype "bidirectional"))
      (node (ref "R23") (pin "1") (pinfunction "1_1") (pintype "passive"))
    )
    (net (code "51") (name "L26") (class "Default")
      (node (ref "B14") (pin "P$2") (pinfunction "K1_P$2") (pintype "bidirectional"))
      (node (ref "R22") (pin "1") (pinfunction "1_1") (pintype "passive"))
    )
    (net (code "52") (name "L27") (class "Default")
      (node (ref "B14") (pin "P$3") (pinfunction "K2_P$3") (pintype "bidirectional"))
      (node (ref "R21") (pin "1") (pinfunction "1_1") (pintype "passive"))
    )
    (net (code "53") (name "L28") (class "Default")
      (node (ref "B15") (pin "P$2") (pinfunction "K1_P$2") (pintype "bidirectional"))
      (node (ref "R4") (pin "1") (pinfunction "1_1") (pintype "passive"))
    )
    (net (code "54") (name "L29") (class "Default")
      (node (ref "B15") (pin "P$3") (pinfunction "K2_P$3") (pintype "bidirectional"))
      (node (ref "R3") (pin "1") (pinfunction "1_1") (pintype "passive"))
    )
    (net (code "55") (name "L30") (class "Default")
      (node (ref "B16") (pin "P$2") (pinfunction "K1_P$2") (pintype "bidirectional"))
      (node (ref "B16ALT") (pin "P$2") (pinfunction "K1_P$2") (pintype "bidirectional"))
      (node (ref "R2") (pin "1") (pinfunction "1_1") (pintype "passive"))
    )
    (net (code "56") (name "L31") (class "Default")
      (node (ref "B16") (pin "P$3") (pinfunction "K2_P$3") (pintype "bidirectional"))
      (node (ref "B16ALT") (pin "P$3") (pinfunction "K2_P$3") (pintype "bidirectional"))
      (node (ref "R1") (pin "1") (pinfunction "1_1") (pintype "passive"))
    )
    (net (code "57") (name "Net-(IC2-L0)") (class "Default")
      (node (ref "IC2") (pin "6") (pinfunction "L0_6") (pintype "output"))
      (node (ref "R20") (pin "2") (pinfunction "2_2") (pintype "passive"))
    )
    (net (code "58") (name "Net-(IC2-L1)") (class "Default")
      (node (ref "IC2") (pin "7") (pinfunction "L1_7") (pintype "output"))
      (node (ref "R19") (pin "2") (pinfunction "2_2") (pintype "passive"))
    )
    (net (code "59") (name "Net-(IC2-L2)") (class "Default")
      (node (ref "IC2") (pin "8") (pinfunction "L2_8") (pintype "output"))
      (node (ref "R18") (pin "2") (pinfunction "2_2") (pintype "passive"))
    )
    (net (code "60") (name "Net-(IC2-L3)") (class "Default")
      (node (ref "IC2") (pin "9") (pinfunction "L3_9") (pintype "output"))
      (node (ref "R17") (pin "2") (pinfunction "2_2") (pintype "passive"))
    )
    (net (code "61") (name "Net-(IC2-L4)") (class "Default")
      (node (ref "IC2") (pin "10") (pinfunction "L4_10") (pintype "output"))
      (node (ref "R16") (pin "2") (pinfunction "2_2") (pintype "passive"))
    )
    (net (code "62") (name "Net-(IC2-L5)") (class "Default")
      (node (ref "IC2") (pin "11") (pinfunction "L5_11") (pintype "output"))
      (node (ref "R15") (pin "2") (pinfunction "2_2") (pintype "passive"))
    )
    (net (code "63") (name "Net-(IC2-L6)") (class "Default")
      (node (ref "IC2") (pin "12") (pinfunction "L6_12") (pintype "output"))
      (node (ref "R14") (pin "2") (pinfunction "2_2") (pintype "passive"))
    )
    (net (code "64") (name "Net-(IC2-L7)") (class "Default")
      (node (ref "IC2") (pin "13") (pinfunction "L7_13") (pintype "output"))
      (node (ref "R13") (pin "2") (pinfunction "2_2") (pintype "passive"))
    )
    (net (code "65") (name "Net-(IC2-L8)") (class "Default")
      (node (ref "IC2") (pin "15") (pinfunction "L8_15") (pintype "output"))
      (node (ref "R12") (pin "2") (pinfunction "2_2") (pintype "passive"))
    )
    (net (code "66") (name "Net-(IC2-L9)") (class "Default")
      (node (ref "IC2") (pin "16") (pinfunction "L9_16") (pintype "output"))
      (node (ref "R11") (pin "2") (pinfunction "2_2") (pintype "passive"))
    )
    (net (code "67") (name "Net-(IC2-L10)") (class "Default")
      (node (ref "IC2") (pin "17") (pinfunction "L10_17") (pintype "output"))
      (node (ref "R10") (pin "2") (pinfunction "2_2") (pintype "passive"))
    )
    (net (code "68") (name "Net-(IC2-L11)") (class "Default")
      (node (ref "IC2") (pin "18") (pinfunction "L11_18") (pintype "output"))
      (node (ref "R9") (pin "2") (pinfunction "2_2") (pintype "passive"))
    )
    (net (code "69") (name "Net-(IC2-L12)") (class "Default")
      (node (ref "IC2") (pin "19") (pinfunction "L12_19") (pintype "output"))
      (node (ref "R8") (pin "2") (pinfunction "2_2") (pintype "passive"))
    )
    (net (code "70") (name "Net-(IC2-L13)") (class "Default")
      (node (ref "IC2") (pin "20") (pinfunction "L13_20") (pintype "output"))
      (node (ref "R7") (pin "2") (pinfunction "2_2") (pintype "passive"))
    )
    (net (code "71") (name "Net-(IC2-L14)") (class "Default")
      (node (ref "IC2") (pin "21") (pinfunction "L14_21") (pintype "output"))
      (node (ref "R6") (pin "2") (pinfunction "2_2") (pintype "passive"))
    )
    (net (code "72") (name "Net-(IC2-L15)") (class "Default")
      (node (ref "IC2") (pin "22") (pinfunction "L15_22") (pintype "output"))
      (node (ref "R5") (pin "2") (pinfunction "2_2") (pintype "passive"))
    )
    (net (code "73") (name "Net-(IC3-L0)") (class "Default")
      (node (ref "IC3") (pin "6") (pinfunction "L0_6") (pintype "output"))
      (node (ref "R32") (pin "2") (pinfunction "2_2") (pintype "passive"))
    )
    (net (code "74") (name "Net-(IC3-L1)") (class "Default")
      (node (ref "IC3") (pin "7") (pinfunction "L1_7") (pintype "output"))
      (node (ref "R31") (pin "2") (pinfunction "2_2") (pintype "passive"))
    )
    (net (code "75") (name "Net-(IC3-L2)") (class "Default")
      (node (ref "IC3") (pin "8") (pinfunction "L2_8") (pintype "output"))
      (node (ref "R30") (pin "2") (pinfunction "2_2") (pintype "passive"))
    )
    (net (code "76") (name "Net-(IC3-L3)") (class "Default")
      (node (ref "IC3") (pin "9") (pinfunction "L3_9") (pintype "output"))
      (node (ref "R29") (pin "2") (pinfunction "2_2") (pintype "passive"))
    )
    (net (code "77") (name "Net-(IC3-L4)") (class "Default")
      (node (ref "IC3") (pin "10") (pinfunction "L4_10") (pintype "output"))
      (node (ref "R28") (pin "2") (pinfunction "2_2") (pintype "passive"))
    )
    (net (code "78") (name "Net-(IC3-L5)") (class "Default")
      (node (ref "IC3") (pin "11") (pinfunction "L5_11") (pintype "output"))
      (node (ref "R27") (pin "2") (pinfunction "2_2") (pintype "passive"))
    )
    (net (code "79") (name "Net-(IC3-L6)") (class "Default")
      (node (ref "IC3") (pin "12") (pinfunction "L6_12") (pintype "output"))
      (node (ref "R26") (pin "2") (pinfunction "2_2") (pintype "passive"))
    )
    (net (code "80") (name "Net-(IC3-L7)") (class "Default")
      (node (ref "IC3") (pin "13") (pinfunction "L7_13") (pintype "output"))
      (node (ref "R25") (pin "2") (pinfunction "2_2") (pintype "passive"))
    )
    (net (code "81") (name "Net-(IC3-L8)") (class "Default")
      (node (ref "IC3") (pin "15") (pinfunction "L8_15") (pintype "output"))
      (node (ref "R24") (pin "2") (pinfunction "2_2") (pintype "passive"))
    )
    (net (code "82") (name "Net-(IC3-L9)") (class "Default")
      (node (ref "IC3") (pin "16") (pinfunction "L9_16") (pintype "output"))
      (node (ref "R23") (pin "2") (pinfunction "2_2") (pintype "passive"))
    )
    (net (code "83") (name "Net-(IC3-L10)") (class "Default")
      (node (ref "IC3") (pin "17") (pinfunction "L10_17") (pintype "output"))
      (node (ref "R22") (pin "2") (pinfunction "2_2") (pintype "passive"))
    )
    (net (code "84") (name "Net-(IC3-L11)") (class "Default")
      (node (ref "IC3") (pin "18") (pinfunction "L11_18") (pintype "output"))
      (node (ref "R21") (pin "2") (pinfunction "2_2") (pintype "passive"))
    )
    (net (code "85") (name "Net-(IC3-L12)") (class "Default")
      (node (ref "IC3") (pin "19") (pinfunction "L12_19") (pintype "output"))
      (node (ref "R4") (pin "2") (pinfunction "2_2") (pintype "passive"))
    )
    (net (code "86") (name "Net-(IC3-L13)") (class "Default")
      (node (ref "IC3") (pin "20") (pinfunction "L13_20") (pintype "output"))
      (node (ref "R3") (pin "2") (pinfunction "2_2") (pintype "passive"))
    )
    (net (code "87") (name "Net-(IC3-L14)") (class "Default")
      (node (ref "IC3") (pin "21") (pinfunction "L14_21") (pintype "output"))
      (node (ref "R2") (pin "2") (pinfunction "2_2") (pintype "passive"))
    )
    (net (code "88") (name "Net-(IC3-L15)") (class "Default")
      (node (ref "IC3") (pin "22") (pinfunction "L15_22") (pintype "output"))
      (node (ref "R1") (pin "2") (pinfunction "2_2") (pintype "passive"))
    )
    (net (code "89") (name "SDI_MOSI") (class "Default")
      (node (ref "SERIAL") (pin "8") (pinfunction "8_8") (pintype "passive"))
    )
    (net (code "90") (name "SDI_SCLK") (class "Default")
      (node (ref "SERIAL") (pin "7") (pinfunction "7_7") (pintype "passive"))
    )
    (net (code "91") (name "SLIDER_IN") (class "Default")
      (node (ref "SERIAL") (pin "5") (pinfunction "5_5") (pintype "passive"))
    )
    (net (code "92") (name "unconnected-(IC1-INTA-Pad20)") (class "Default")
      (node (ref "IC1") (pin "20") (pinfunction "INTA_20") (pintype "output"))
    )
    (net (code "93") (name "unconnected-(IC1-INTB-Pad19)") (class "Default")
      (node (ref "IC1") (pin "19") (pinfunction "INTB_19") (pintype "output"))
    )
  )
)
